# DIGITAL_INP.net
KiCad netlist of a schematic drawn in Altium Designer
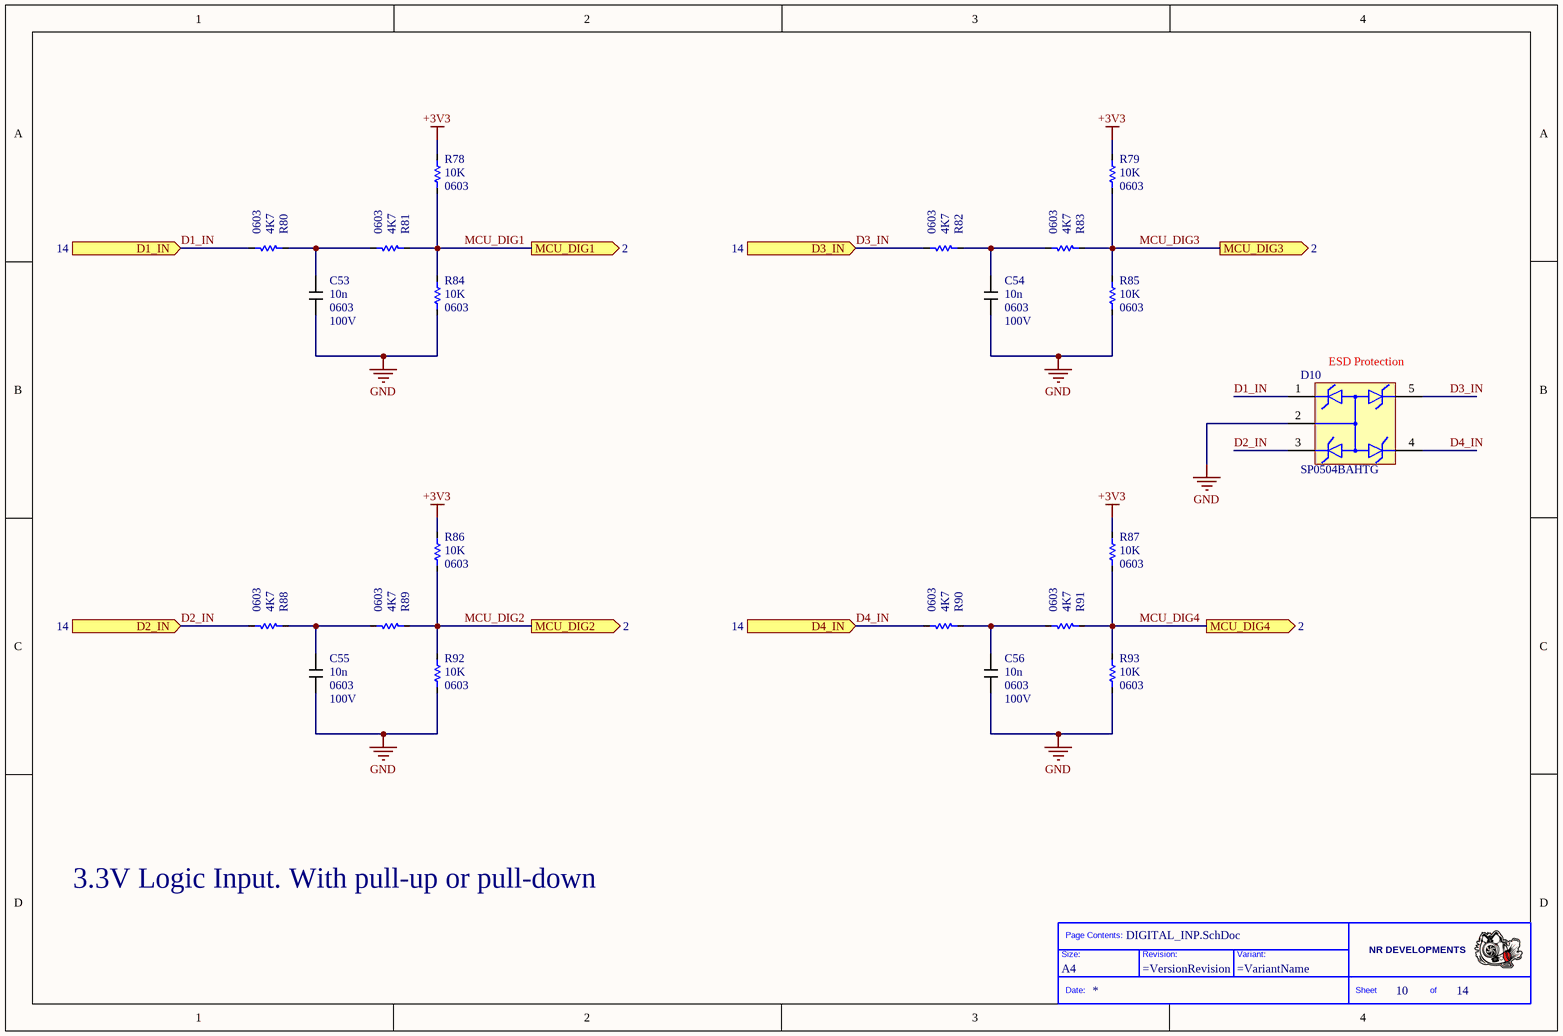
[diagram p0: DIGITAL_INP.SchDoc]

(export (version "E")
  (design (tool "Eeschema 10.0.6"))
  (components
    (comp (ref "C53")
      (value "10n")
      (footprint "CAPC1608X09M")
      (fields
        (field (name "CASE") "0603")
        (field (name "VOLTAGE") "100V")
        (field (name "MANUFACTURER") "KEMET")
        (field (name "PARTNUMBER") "C0603C103K1RACTU")
        (field (name "Comment") "CAP")
      )
      (libsource (lib "My_LIB") (part "CAP"))
    )
    (comp (ref "C54")
      (value "10n")
      (footprint "CAPC1608X09M")
      (fields
        (field (name "CASE") "0603")
        (field (name "VOLTAGE") "100V")
        (field (name "MANUFACTURER") "KEMET")
        (field (name "PARTNUMBER") "C0603C103K1RACTU")
        (field (name "Comment") "CAP")
      )
      (libsource (lib "My_LIB") (part "CAP"))
    )
    (comp (ref "C55")
      (value "10n")
      (footprint "CAPC1608X09M")
      (fields
        (field (name "CASE") "0603")
        (field (name "VOLTAGE") "100V")
        (field (name "MANUFACTURER") "KEMET")
        (field (name "PARTNUMBER") "C0603C103K1RACTU")
        (field (name "Comment") "CAP")
      )
      (libsource (lib "My_LIB") (part "CAP"))
    )
    (comp (ref "C56")
      (value "10n")
      (footprint "CAPC1608X09M")
      (fields
        (field (name "CASE") "0603")
        (field (name "VOLTAGE") "100V")
        (field (name "MANUFACTURER") "KEMET")
        (field (name "PARTNUMBER") "C0603C103K1RACTU")
        (field (name "Comment") "CAP")
      )
      (libsource (lib "My_LIB") (part "CAP"))
    )
    (comp (ref "D10")
      (value "SP0504BAHTG")
      (footprint "SOT95P280X145-5N")
      (fields (field (name "MANUFACTURER") "Littelfuse") (field (name "Comment") "Diode TVS"))
      (libsource (lib "My_LIB") (part "SP0504BAHTG"))
    )
    (comp (ref "R78")
      (value "10K")
      (footprint "RESC1608X06M")
      (fields
        (field (name "CASE") "0603")
        (field (name "MANUFACTURER") "YAGEO")
        (field (name "PARTNUMBER") "AC0603FR-0710KL")
        (field (name "Comment") "Res")
      )
      (libsource (lib "My_LIB") (part "Resistor"))
    )
    (comp (ref "R79")
      (value "10K")
      (footprint "RESC1608X06M")
      (fields
        (field (name "CASE") "0603")
        (field (name "MANUFACTURER") "YAGEO")
        (field (name "PARTNUMBER") "AC0603FR-0710KL")
        (field (name "Comment") "Res")
      )
      (libsource (lib "My_LIB") (part "Resistor"))
    )
    (comp (ref "R80")
      (value "4K7")
      (footprint "RESC1608X06M")
      (fields
        (field (name "CASE") "0603")
        (field (name "MANUFACTURER") "YAGEO")
        (field (name "PARTNUMBER") " RC0603FR-074K7L")
        (field (name "Comment") "Res")
      )
      (libsource (lib "My_LIB") (part "Resistor"))
    )
    (comp (ref "R81")
      (value "4K7")
      (footprint "RESC1608X06M")
      (fields
        (field (name "CASE") "0603")
        (field (name "MANUFACTURER") "YAGEO")
        (field (name "PARTNUMBER") " RC0603FR-074K7L")
        (field (name "Comment") "Res")
      )
      (libsource (lib "My_LIB") (part "Resistor"))
    )
    (comp (ref "R82")
      (value "4K7")
      (footprint "RESC1608X06M")
      (fields
        (field (name "CASE") "0603")
        (field (name "MANUFACTURER") "YAGEO")
        (field (name "PARTNUMBER") " RC0603FR-074K7L")
        (field (name "Comment") "Res")
      )
      (libsource (lib "My_LIB") (part "Resistor"))
    )
    (comp (ref "R83")
      (value "4K7")
      (footprint "RESC1608X06M")
      (fields
        (field (name "CASE") "0603")
        (field (name "MANUFACTURER") "YAGEO")
        (field (name "PARTNUMBER") " RC0603FR-074K7L")
        (field (name "Comment") "Res")
      )
      (libsource (lib "My_LIB") (part "Resistor"))
    )
    (comp (ref "R84")
      (value "10K")
      (footprint "RESC1608X06M")
      (fields
        (field (name "CASE") "0603")
        (field (name "MANUFACTURER") "YAGEO")
        (field (name "PARTNUMBER") "AC0603FR-0710KL")
        (field (name "Comment") "Res")
      )
      (libsource (lib "My_LIB") (part "Resistor"))
    )
    (comp (ref "R85")
      (value "10K")
      (footprint "RESC1608X06M")
      (fields
        (field (name "CASE") "0603")
        (field (name "MANUFACTURER") "YAGEO")
        (field (name "PARTNUMBER") "AC0603FR-0710KL")
        (field (name "Comment") "Res")
      )
      (libsource (lib "My_LIB") (part "Resistor"))
    )
    (comp (ref "R86")
      (value "10K")
      (footprint "RESC1608X06M")
      (fields
        (field (name "CASE") "0603")
        (field (name "MANUFACTURER") "YAGEO")
        (field (name "PARTNUMBER") "AC0603FR-0710KL")
        (field (name "Comment") "Res")
      )
      (libsource (lib "My_LIB") (part "Resistor"))
    )
    (comp (ref "R87")
      (value "10K")
      (footprint "RESC1608X06M")
      (fields
        (field (name "CASE") "0603")
        (field (name "MANUFACTURER") "YAGEO")
        (field (name "PARTNUMBER") "AC0603FR-0710KL")
        (field (name "Comment") "Res")
      )
      (libsource (lib "My_LIB") (part "Resistor"))
    )
    (comp (ref "R88")
      (value "4K7")
      (footprint "RESC1608X06M")
      (fields
        (field (name "CASE") "0603")
        (field (name "MANUFACTURER") "YAGEO")
        (field (name "PARTNUMBER") " RC0603FR-074K7L")
        (field (name "Comment") "Res")
      )
      (libsource (lib "My_LIB") (part "Resistor"))
    )
    (comp (ref "R89")
      (value "4K7")
      (footprint "RESC1608X06M")
      (fields
        (field (name "CASE") "0603")
        (field (name "MANUFACTURER") "YAGEO")
        (field (name "PARTNUMBER") " RC0603FR-074K7L")
        (field (name "Comment") "Res")
      )
      (libsource (lib "My_LIB") (part "Resistor"))
    )
    (comp (ref "R90")
      (value "4K7")
      (footprint "RESC1608X06M")
      (fields
        (field (name "CASE") "0603")
        (field (name "MANUFACTURER") "YAGEO")
        (field (name "PARTNUMBER") " RC0603FR-074K7L")
        (field (name "Comment") "Res")
      )
      (libsource (lib "My_LIB") (part "Resistor"))
    )
    (comp (ref "R91")
      (value "4K7")
      (footprint "RESC1608X06M")
      (fields
        (field (name "CASE") "0603")
        (field (name "MANUFACTURER") "YAGEO")
        (field (name "PARTNUMBER") " RC0603FR-074K7L")
        (field (name "Comment") "Res")
      )
      (libsource (lib "My_LIB") (part "Resistor"))
    )
    (comp (ref "R92")
      (value "10K")
      (footprint "RESC1608X06M")
      (fields
        (field (name "CASE") "0603")
        (field (name "MANUFACTURER") "YAGEO")
        (field (name "PARTNUMBER") "AC0603FR-0710KL")
        (field (name "Comment") "Res")
      )
      (libsource (lib "My_LIB") (part "Resistor"))
    )
    (comp (ref "R93")
      (value "10K")
      (footprint "RESC1608X06M")
      (fields
        (field (name "CASE") "0603")
        (field (name "MANUFACTURER") "YAGEO")
        (field (name "PARTNUMBER") "AC0603FR-0710KL")
        (field (name "Comment") "Res")
      )
      (libsource (lib "My_LIB") (part "Resistor"))
    )
  )
  (nets
    (net (code "1") (name "+3V3") (class "Default")
      (node (ref "R78") (pin "2") (pinfunction "2_2") (pintype "passive"))
      (node (ref "R79") (pin "2") (pinfunction "2_2") (pintype "passive"))
      (node (ref "R86") (pin "2") (pinfunction "2_2") (pintype "passive"))
      (node (ref "R87") (pin "2") (pinfunction "2_2") (pintype "passive"))
    )
    (net (code "2") (name "/D1_IN") (class "Default")
      (node (ref "D10") (pin "1") (pinfunction "1_1") (pintype "passive"))
      (node (ref "R80") (pin "1") (pinfunction "1_1") (pintype "passive"))
    )
    (net (code "3") (name "/D2_IN") (class "Default")
      (node (ref "D10") (pin "3") (pinfunction "3_3") (pintype "passive"))
      (node (ref "R88") (pin "1") (pinfunction "1_1") (pintype "passive"))
    )
    (net (code "4") (name "/D3_IN") (class "Default")
      (node (ref "D10") (pin "5") (pinfunction "5_5") (pintype "passive"))
      (node (ref "R82") (pin "1") (pinfunction "1_1") (pintype "passive"))
    )
    (net (code "5") (name "/D4_IN") (class "Default")
      (node (ref "D10") (pin "4") (pinfunction "4_4") (pintype "passive"))
      (node (ref "R90") (pin "1") (pinfunction "1_1") (pintype "passive"))
    )
    (net (code "6") (name "/MCU_DIG1") (class "Default")
      (node (ref "R78") (pin "1") (pinfunction "1_1") (pintype "passive"))
      (node (ref "R81") (pin "2") (pinfunction "2_2") (pintype "passive"))
      (node (ref "R84") (pin "2") (pinfunction "2_2") (pintype "passive"))
    )
    (net (code "7") (name "/MCU_DIG2") (class "Default")
      (node (ref "R86") (pin "1") (pinfunction "1_1") (pintype "passive"))
      (node (ref "R89") (pin "2") (pinfunction "2_2") (pintype "passive"))
      (node (ref "R92") (pin "2") (pinfunction "2_2") (pintype "passive"))
    )
    (net (code "8") (name "/MCU_DIG3") (class "Default")
      (node (ref "R79") (pin "1") (pinfunction "1_1") (pintype "passive"))
      (node (ref "R83") (pin "2") (pinfunction "2_2") (pintype "passive"))
      (node (ref "R85") (pin "2") (pinfunction "2_2") (pintype "passive"))
    )
    (net (code "9") (name "/MCU_DIG4") (class "Default")
      (node (ref "R87") (pin "1") (pinfunction "1_1") (pintype "passive"))
      (node (ref "R91") (pin "2") (pinfunction "2_2") (pintype "passive"))
      (node (ref "R93") (pin "2") (pinfunction "2_2") (pintype "passive"))
    )
    (net (code "10") (name "GND") (class "Default")
      (node (ref "C53") (pin "2") (pinfunction "2_2") (pintype "passive"))
      (node (ref "C54") (pin "2") (pinfunction "2_2") (pintype "passive"))
      (node (ref "C55") (pin "2") (pinfunction "2_2") (pintype "passive"))
      (node (ref "C56") (pin "2") (pinfunction "2_2") (pintype "passive"))
      (node (ref "D10") (pin "2") (pinfunction "2_2") (pintype "passive"))
      (node (ref "R84") (pin "1") (pinfunction "1_1") (pintype "passive"))
      (node (ref "R85") (pin "1") (pinfunction "1_1") (pintype "passive"))
      (node (ref "R92") (pin "1") (pinfunction "1_1") (pintype "passive"))
      (node (ref "R93") (pin "1") (pinfunction "1_1") (pintype "passive"))
    )
    (net (code "11") (name "Net-(C53-Pad1)") (class "Default")
      (node (ref "C53") (pin "1") (pinfunction "1_1") (pintype "passive"))
      (node (ref "R80") (pin "2") (pinfunction "2_2") (pintype "passive"))
      (node (ref "R81") (pin "1") (pinfunction "1_1") (pintype "passive"))
    )
    (net (code "12") (name "Net-(C54-Pad1)") (class "Default")
      (node (ref "C54") (pin "1") (pinfunction "1_1") (pintype "passive"))
      (node (ref "R82") (pin "2") (pinfunction "2_2") (pintype "passive"))
      (node (ref "R83") (pin "1") (pinfunction "1_1") (pintype "passive"))
    )
    (net (code "13") (name "Net-(C55-Pad1)") (class "Default")
      (node (ref "C55") (pin "1") (pinfunction "1_1") (pintype "passive"))
      (node (ref "R88") (pin "2") (pinfunction "2_2") (pintype "passive"))
      (node (ref "R89") (pin "1") (pinfunction "1_1") (pintype "passive"))
    )
    (net (code "14") (name "Net-(C56-Pad1)") (class "Default")
      (node (ref "C56") (pin "1") (pinfunction "1_1") (pintype "passive"))
      (node (ref "R90") (pin "2") (pinfunction "2_2") (pintype "passive"))
      (node (ref "R91") (pin "1") (pinfunction "1_1") (pintype "passive"))
    )
  )
)
